# MotherBoard.net
KiCad netlist of a schematic drawn in Altium Designer
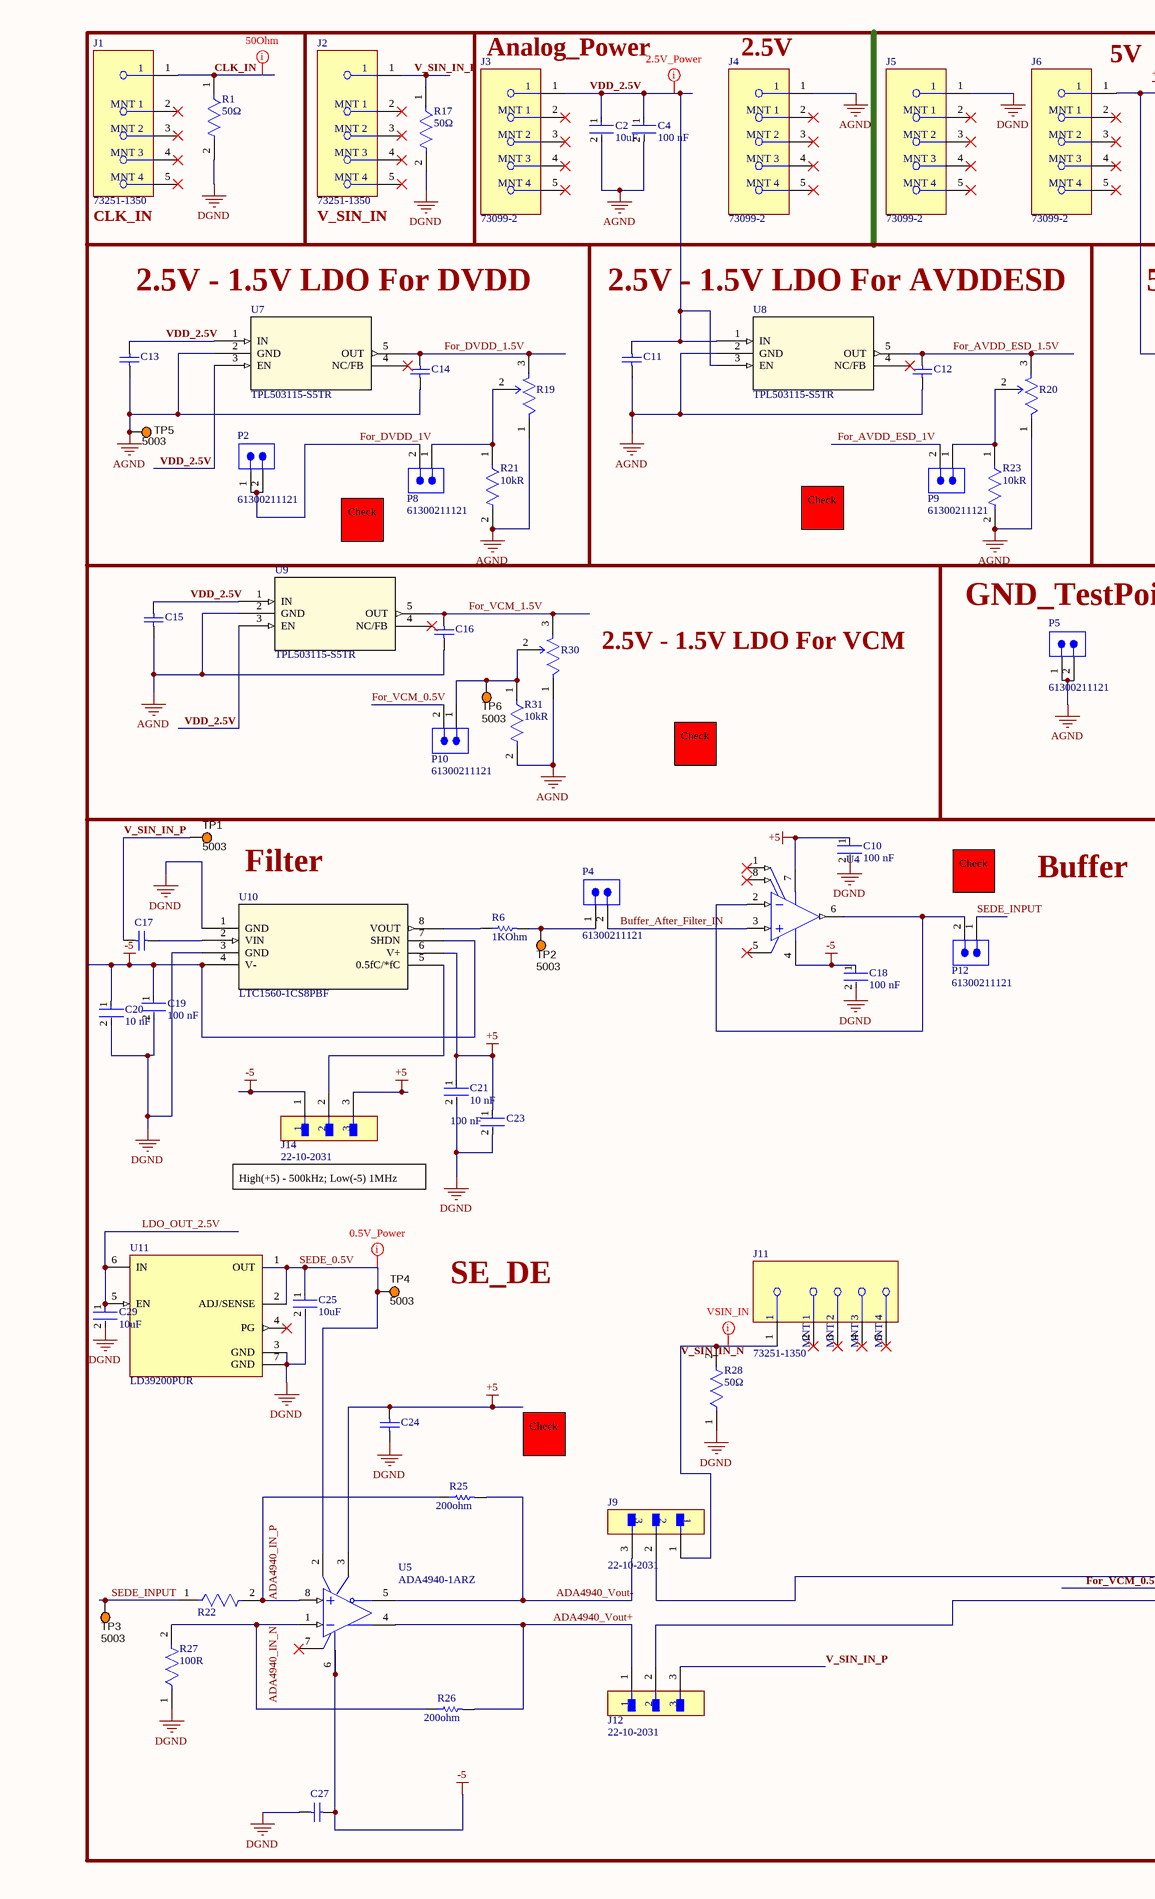
[diagram p0: MotherBoard.SchDoc, left]
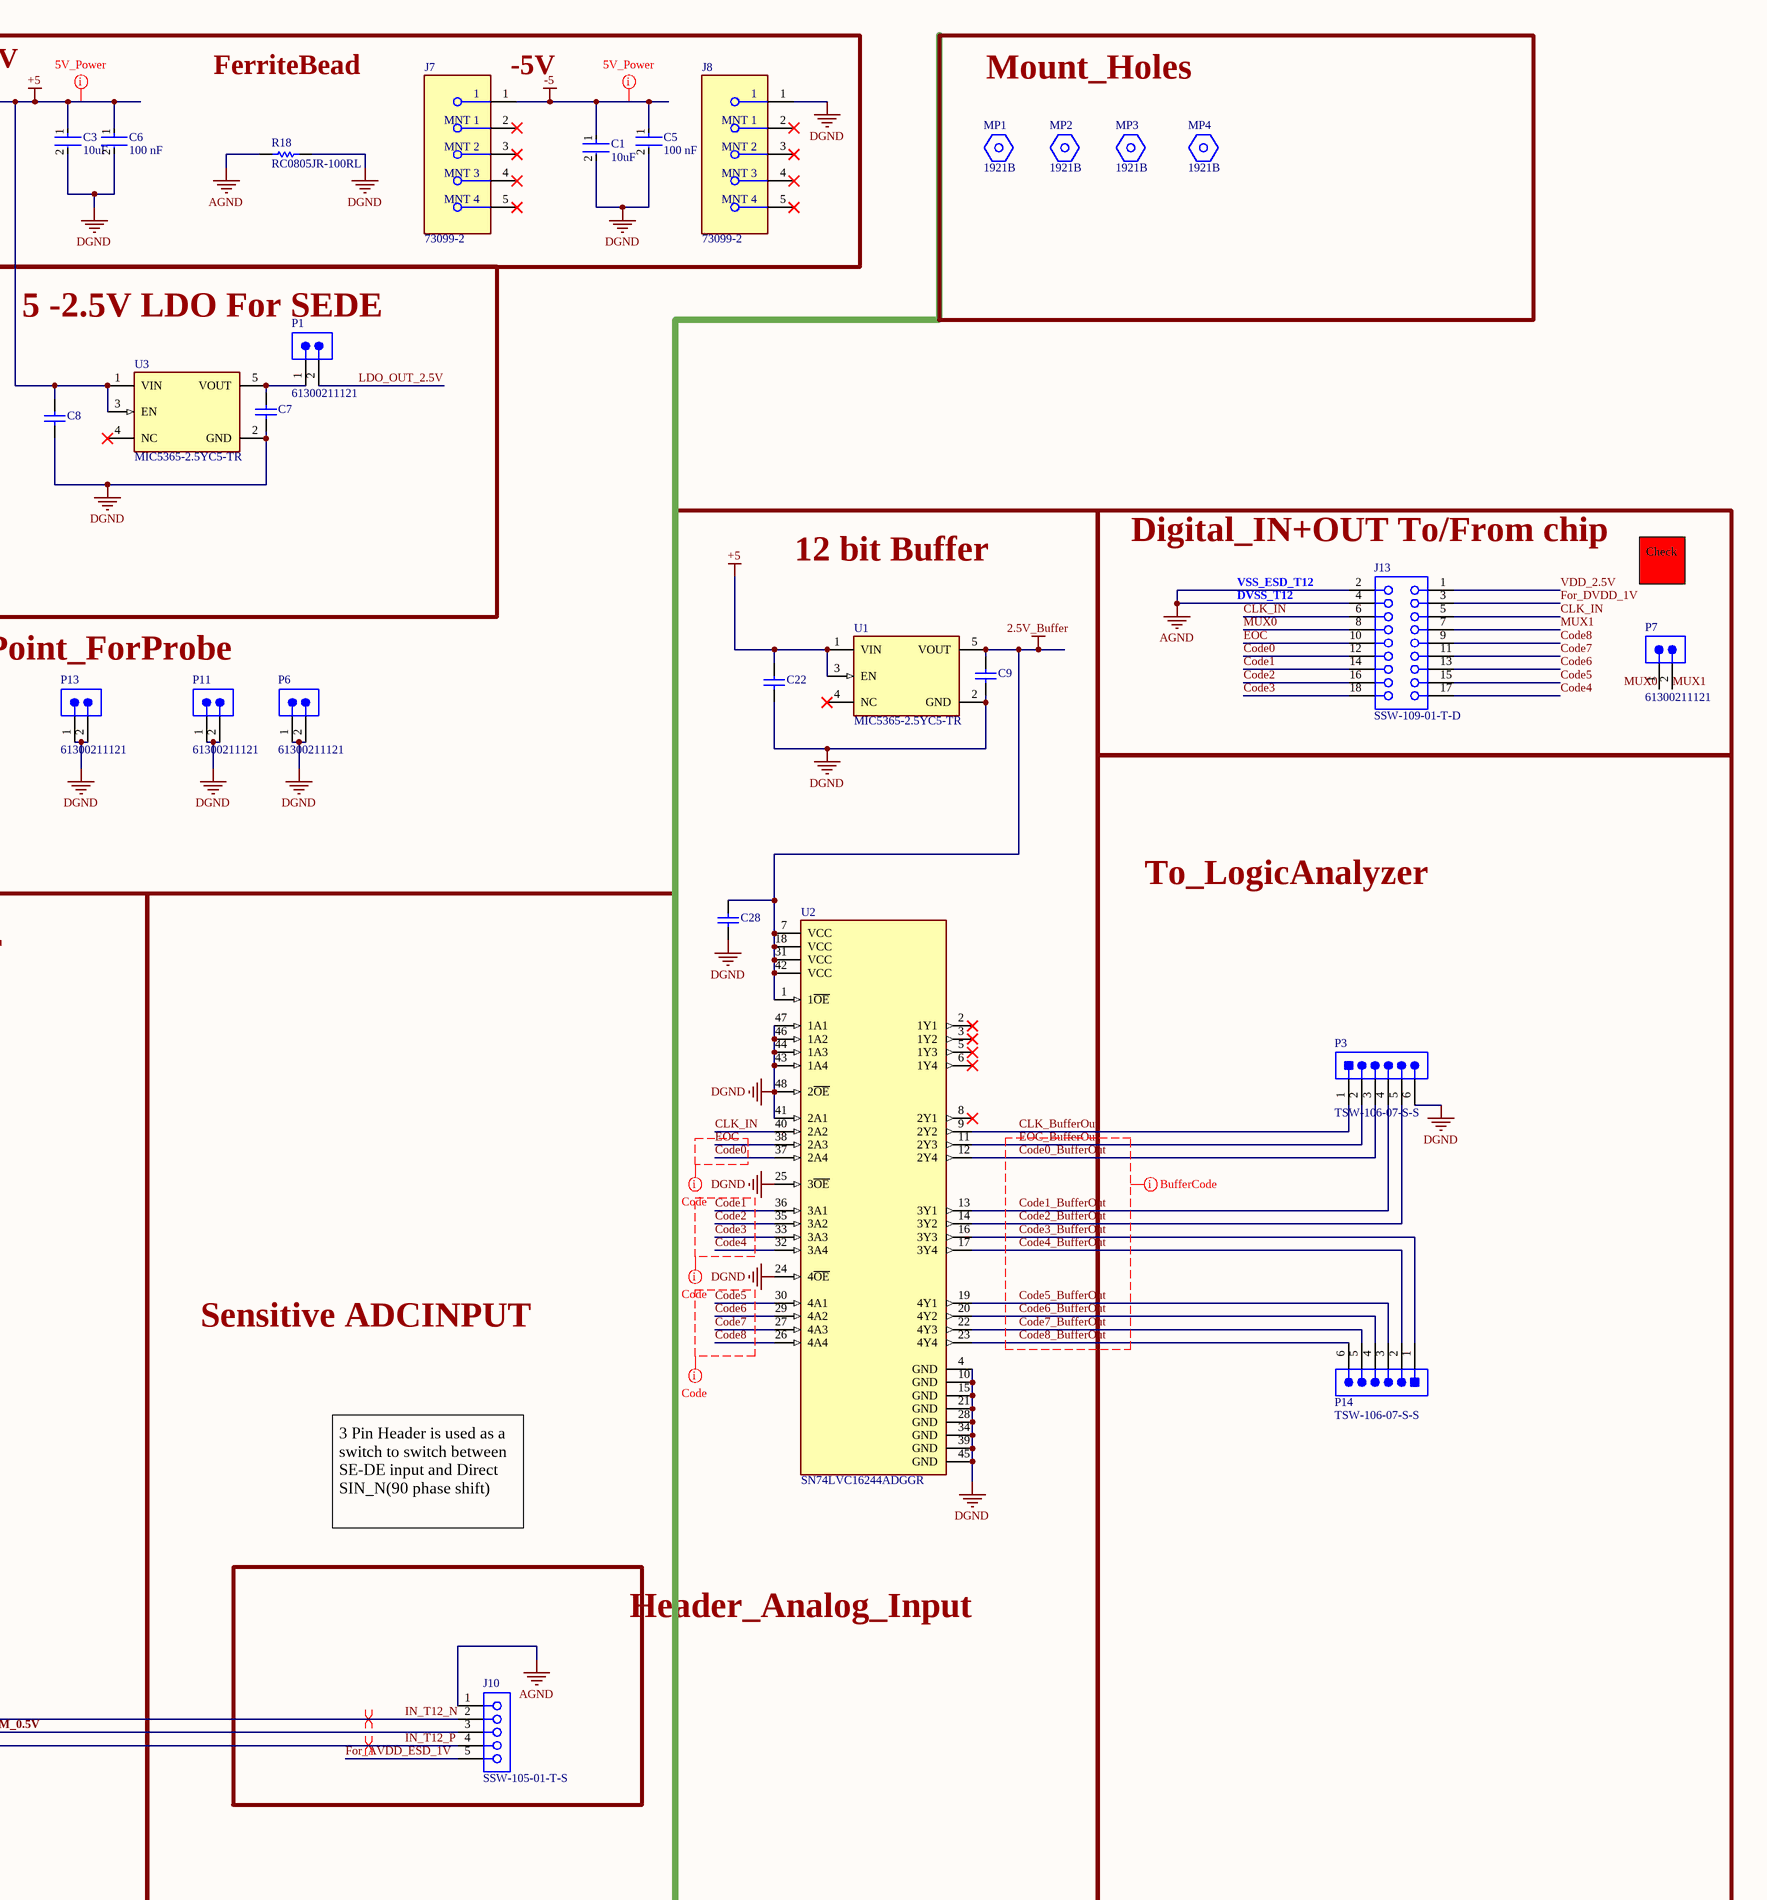
[diagram p1: MotherBoard.SchDoc, right]

(export (version "E")
  (design (tool "Eeschema 10.0.6"))
  (components
    (comp (ref "C1")
      (value "0805ZD106MAT2A")
      (footprint "FP-0805-L_2_01_0_2-W_1_25-MFG")
      (description "General Purpose Ceramic Capacitor, 0805, 10uF, 20%, X5R, 15%, 10V")
      (fields
        (field (name "CAPACITANCE") "10uF")
        (field (name "TOLERANCE") "20%")
        (field (name "VOLTAGE") "10V")
      )
      (libsource (lib "Altium Content Vault") (part "02cd4be3c70576c341d710602a673aa"))
    )
    (comp (ref "C2")
      (value "0805ZD106MAT2A")
      (footprint "FP-0805-L_2_01_0_2-W_1_25-MFG")
      (description "General Purpose Ceramic Capacitor, 0805, 10uF, 20%, X5R, 15%, 10V")
      (fields
        (field (name "CAPACITANCE") "10uF")
        (field (name "TOLERANCE") "20%")
        (field (name "VOLTAGE") "10V")
      )
      (libsource (lib "Altium Content Vault") (part "02cd4be3c70576c341d710602a673aa"))
    )
    (comp (ref "C3")
      (value "0805ZD106MAT2A")
      (footprint "FP-0805-L_2_01_0_2-W_1_25-MFG")
      (description "General Purpose Ceramic Capacitor, 0805, 10uF, 20%, X5R, 15%, 10V")
      (fields
        (field (name "CAPACITANCE") "10uF")
        (field (name "TOLERANCE") "20%")
        (field (name "VOLTAGE") "10V")
      )
      (libsource (lib "Altium Content Vault") (part "02cd4be3c70576c341d710602a673aa"))
    )
    (comp (ref "C4")
      (value "CC0805KRX7R8BB104")
      (footprint "FP-CC0805-0_85-MFG")
      (description "CAP CER 0.1UF 25V X7R 0805")
      (fields
        (field (name "TOLERANCE") "0.1")
        (field (name "MANUFACTURER") "Yageo")
        (field (name "CAPACITANCE") "100 nF")
      )
      (libsource (lib "Altium Content Vault") (part "11868f565c42a9108669ba33697ecf6"))
    )
    (comp (ref "C5")
      (value "CC0805KRX7R8BB104")
      (footprint "FP-CC0805-0_85-MFG")
      (description "CAP CER 0.1UF 25V X7R 0805")
      (fields
        (field (name "TOLERANCE") "0.1")
        (field (name "MANUFACTURER") "Yageo")
        (field (name "CAPACITANCE") "100 nF")
      )
      (libsource (lib "Altium Content Vault") (part "11868f565c42a9108669ba33697ecf6"))
    )
    (comp (ref "C6")
      (value "CC0805KRX7R8BB104")
      (footprint "FP-CC0805-0_85-MFG")
      (description "CAP CER 0.1UF 25V X7R 0805")
      (fields
        (field (name "TOLERANCE") "0.1")
        (field (name "MANUFACTURER") "Yageo")
        (field (name "CAPACITANCE") "100 nF")
      )
      (libsource (lib "Altium Content Vault") (part "11868f565c42a9108669ba33697ecf6"))
    )
    (comp (ref "C7")
      (value "0805ZC105KAZ2A")
      (footprint "CAPC2013X140X50LL20T25")
      (fields (field (name "MANUFACTURER") "AVX Interconnect / Elco"))
      (libsource (lib "Altium Content Vault") (part "CAP"))
    )
    (comp (ref "C8")
      (value "0805ZC105KAZ2A")
      (footprint "CAPC2013X140X50LL20T25")
      (fields (field (name "MANUFACTURER") "AVX Interconnect / Elco"))
      (libsource (lib "Altium Content Vault") (part "CAP"))
    )
    (comp (ref "C9")
      (value "0805ZC105KAZ2A")
      (footprint "CAPC2013X140X50LL20T25")
      (fields (field (name "MANUFACTURER") "AVX Interconnect / Elco"))
      (libsource (lib "Altium Content Vault") (part "CAP"))
    )
    (comp (ref "C10")
      (value "CC0805KRX7R8BB104")
      (footprint "FP-CC0805-0_85-MFG")
      (description "CAP CER 0.1UF 25V X7R 0805")
      (fields
        (field (name "TOLERANCE") "0.1")
        (field (name "MANUFACTURER") "Yageo")
        (field (name "CAPACITANCE") "100 nF")
      )
      (libsource (lib "Altium Content Vault") (part "11868f565c42a9108669ba33697ecf6"))
    )
    (comp (ref "C11")
      (value "0805ZC105KAZ2A")
      (footprint "CAPC2013X140X50LL20T25")
      (fields (field (name "MANUFACTURER") "AVX Interconnect / Elco"))
      (libsource (lib "Altium Content Vault") (part "CAP"))
    )
    (comp (ref "C12")
      (value "0805ZC105KAZ2A")
      (footprint "CAPC2013X140X50LL20T25")
      (fields (field (name "MANUFACTURER") "AVX Interconnect / Elco"))
      (libsource (lib "Altium Content Vault") (part "CAP"))
    )
    (comp (ref "C13")
      (value "0805ZC105KAZ2A")
      (footprint "CAPC2013X140X50LL20T25")
      (fields (field (name "MANUFACTURER") "AVX Interconnect / Elco"))
      (libsource (lib "Altium Content Vault") (part "CAP"))
    )
    (comp (ref "C14")
      (value "0805ZC105KAZ2A")
      (footprint "CAPC2013X140X50LL20T25")
      (fields (field (name "MANUFACTURER") "AVX Interconnect / Elco"))
      (libsource (lib "Altium Content Vault") (part "CAP"))
    )
    (comp (ref "C15")
      (value "0805ZC105KAZ2A")
      (footprint "CAPC2013X140X50LL20T25")
      (fields (field (name "MANUFACTURER") "AVX Interconnect / Elco"))
      (libsource (lib "Altium Content Vault") (part "CAP"))
    )
    (comp (ref "C16")
      (value "0805ZC105KAZ2A")
      (footprint "CAPC2013X140X50LL20T25")
      (fields (field (name "MANUFACTURER") "AVX Interconnect / Elco"))
      (libsource (lib "Altium Content Vault") (part "CAP"))
    )
    (comp (ref "C17")
      (value "VJ0805D561KXBAJ")
      (footprint "CAPC2013X145X48ML20T23")
      (fields (field (name "MANUFACTURER") "Vitramon"))
      (libsource (lib "Altium Content Vault") (part "CAP"))
    )
    (comp (ref "C18")
      (value "CC0805KRX7R8BB104")
      (footprint "FP-CC0805-0_85-MFG")
      (description "CAP CER 0.1UF 25V X7R 0805")
      (fields
        (field (name "TOLERANCE") "0.1")
        (field (name "MANUFACTURER") "Yageo")
        (field (name "CAPACITANCE") "100 nF")
      )
      (libsource (lib "Altium Content Vault") (part "11868f565c42a9108669ba33697ecf6"))
    )
    (comp (ref "C19")
      (value "CC0805KRX7R8BB104")
      (footprint "FP-CC0805-0_85-MFG")
      (description "CAP CER 0.1UF 25V X7R 0805")
      (fields
        (field (name "TOLERANCE") "0.1")
        (field (name "MANUFACTURER") "Yageo")
        (field (name "CAPACITANCE") "100 nF")
      )
      (libsource (lib "Altium Content Vault") (part "11868f565c42a9108669ba33697ecf6"))
    )
    (comp (ref "C20")
      (value "CC0805KRX7R9BB103")
      (footprint "FP-CC0805-0_85-MFG")
      (description "CAP CER 10000PF 50V X7R 0805")
      (fields
        (field (name "CAPACITANCE") "10 nF")
        (field (name "OCTOPART") "https://octopart.com/cc0805krx7r9bb103-yageo-192989")
        (field (name "MANUFACTURER") "Yageo")
      )
      (libsource (lib "Altium Content Vault") (part "11868f565c42a9108669ba33697ecf6"))
    )
    (comp (ref "C21")
      (value "CC0805KRX7R9BB103")
      (footprint "FP-CC0805-0_85-MFG")
      (description "CAP CER 10000PF 50V X7R 0805")
      (fields
        (field (name "CAPACITANCE") "10 nF")
        (field (name "OCTOPART") "https://octopart.com/cc0805krx7r9bb103-yageo-192989")
        (field (name "MANUFACTURER") "Yageo")
      )
      (libsource (lib "Altium Content Vault") (part "11868f565c42a9108669ba33697ecf6"))
    )
    (comp (ref "C22")
      (value "0805ZC105KAZ2A")
      (footprint "CAPC2013X140X50LL20T25")
      (fields (field (name "MANUFACTURER") "AVX Interconnect / Elco"))
      (libsource (lib "Altium Content Vault") (part "CAP"))
    )
    (comp (ref "C23")
      (value "CC0805KRX7R8BB104")
      (footprint "FP-CC0805-0_85-MFG")
      (description "CAP CER 0.1UF 25V X7R 0805")
      (fields
        (field (name "TOLERANCE") "0.1")
        (field (name "MANUFACTURER") "Yageo")
        (field (name "CAPACITANCE") "100 nF")
      )
      (libsource (lib "Altium Content Vault") (part "11868f565c42a9108669ba33697ecf6"))
    )
    (comp (ref "C24")
      (value "0805ZC105KAZ2A")
      (footprint "CAPC2013X140X50LL20T25")
      (fields (field (name "MANUFACTURER") "AVX Interconnect / Elco"))
      (libsource (lib "Altium Content Vault") (part "CAP"))
    )
    (comp (ref "C25")
      (value "0805ZD106MAT2A")
      (footprint "FP-0805-L_2_01_0_2-W_1_25-MFG")
      (description "General Purpose Ceramic Capacitor, 0805, 10uF, 20%, X5R, 15%, 10V")
      (fields
        (field (name "CAPACITANCE") "10uF")
        (field (name "TOLERANCE") "20%")
        (field (name "VOLTAGE") "10V")
      )
      (libsource (lib "Altium Content Vault") (part "02cd4be3c70576c341d710602a673aa"))
    )
    (comp (ref "C27")
      (value "0805ZC105KAZ2A")
      (footprint "CAPC2013X140X50LL20T25")
      (fields (field (name "MANUFACTURER") "AVX Interconnect / Elco"))
      (libsource (lib "Altium Content Vault") (part "CAP"))
    )
    (comp (ref "C28")
      (value "0805ZC105KAZ2A")
      (footprint "CAPC2013X140X50LL20T25")
      (fields (field (name "MANUFACTURER") "AVX Interconnect / Elco"))
      (libsource (lib "Altium Content Vault") (part "CAP"))
    )
    (comp (ref "C29")
      (value "0805ZD106MAT2A")
      (footprint "FP-0805-L_2_01_0_2-W_1_25-MFG")
      (description "General Purpose Ceramic Capacitor, 0805, 10uF, 20%, X5R, 15%, 10V")
      (fields
        (field (name "CAPACITANCE") "10uF")
        (field (name "TOLERANCE") "20%")
        (field (name "VOLTAGE") "10V")
      )
      (libsource (lib "Altium Content Vault") (part "02cd4be3c70576c341d710602a673aa"))
    )
    (comp (ref "J1")
      (value "73251-1350")
      (footprint "FP-73251-1350-MFG")
      (description "CONN SMA JACK STR 50 OHM SMD")
      (fields
        (field (name "OCTOPART") "https://octopart.com/73251-1350-molex-5414390")
        (field (name "MANUFACTURER") "Molex")
      )
      (libsource (lib "Altium Content Vault") (part "474d33b8a96b1ade9ed6dd87a2b06d4"))
    )
    (comp (ref "J2")
      (value "73251-1350")
      (footprint "FP-73251-1350-MFG")
      (description "CONN SMA JACK STR 50 OHM SMD")
      (fields
        (field (name "OCTOPART") "https://octopart.com/73251-1350-molex-5414390")
        (field (name "MANUFACTURER") "Molex")
      )
      (libsource (lib "Altium Content Vault") (part "474d33b8a96b1ade9ed6dd87a2b06d4"))
    )
    (comp (ref "J3")
      (value "73099-2")
      (footprint "FP-73099-2-MFG")
      (description "R/A 4MM MOUNTG SAFE JACK/PCB RED")
      (libsource (lib "Altium Content Vault") (part "9c40ac4d87bbbe9fcb330bd20f98ca3"))
    )
    (comp (ref "J4")
      (value "73099-2")
      (footprint "FP-73099-2-MFG")
      (description "R/A 4MM MOUNTG SAFE JACK/PCB RED")
      (libsource (lib "Altium Content Vault") (part "9c40ac4d87bbbe9fcb330bd20f98ca3"))
    )
    (comp (ref "J5")
      (value "73099-2")
      (footprint "FP-73099-2-MFG")
      (description "R/A 4MM MOUNTG SAFE JACK/PCB RED")
      (libsource (lib "Altium Content Vault") (part "9c40ac4d87bbbe9fcb330bd20f98ca3"))
    )
    (comp (ref "J6")
      (value "73099-2")
      (footprint "FP-73099-2-MFG")
      (description "R/A 4MM MOUNTG SAFE JACK/PCB RED")
      (libsource (lib "Altium Content Vault") (part "9c40ac4d87bbbe9fcb330bd20f98ca3"))
    )
    (comp (ref "J7")
      (value "73099-2")
      (footprint "FP-73099-2-MFG")
      (description "R/A 4MM MOUNTG SAFE JACK/PCB RED")
      (libsource (lib "Altium Content Vault") (part "9c40ac4d87bbbe9fcb330bd20f98ca3"))
    )
    (comp (ref "J8")
      (value "73099-2")
      (footprint "FP-73099-2-MFG")
      (description "R/A 4MM MOUNTG SAFE JACK/PCB RED")
      (libsource (lib "Altium Content Vault") (part "9c40ac4d87bbbe9fcb330bd20f98ca3"))
    )
    (comp (ref "J9")
      (value "22-10-2031")
      (footprint "FP-22-10-2031-MFG")
      (description "CONN HEADER VERT 3POS 2.54MM")
      (libsource (lib "") (part "0d3f023dd272f625e17a2be33dea85f_1"))
    )
    (comp (ref "J10")
      (value "SSW-105-01-T-S")
      (footprint "SMTC-SSW-105-01-X-S")
      (description "SQ Post Socket, Through-hole, Vertical, -55 to 105 degC, 2.54mm Pitch, 5-Pin, Female, RoHS")
      (fields (field (name "MANUFACTURER") "Samtec"))
      (libsource (lib "Altium Content Vault") (part "SMTC-SSW-105-X-X-S"))
    )
    (comp (ref "J11")
      (value "73251-1350")
      (footprint "FP-73251-1350-MFG")
      (description "CONN SMA JACK STR 50 OHM SMD")
      (fields
        (field (name "OCTOPART") "https://octopart.com/73251-1350-molex-5414390")
        (field (name "MANUFACTURER") "Molex")
      )
      (libsource (lib "") (part "474d33b8a96b1ade9ed6dd87a2b06d4_1"))
    )
    (comp (ref "J12")
      (value "22-10-2031")
      (footprint "FP-22-10-2031-MFG")
      (description "CONN HEADER VERT 3POS 2.54MM")
      (libsource (lib "Altium Content Vault") (part "0d3f023dd272f625e17a2be33dea85f"))
    )
    (comp (ref "J13")
      (value "SSW-109-01-T-D")
      (footprint "SMTC-SSW-109-01-X-D")
      (description "SQ Post Socket, Through-hole, Vertical, -55 to 105 degC, 2.54mm Pitch, 18-Pin, Female, RoHS")
      (fields (field (name "MANUFACTURER") "Samtec"))
      (libsource (lib "Altium Content Vault") (part "SMTC-SSW-109-01-X-D"))
    )
    (comp (ref "J14")
      (value "22-10-2031")
      (footprint "FP-22-10-2031-MFG")
      (description "CONN HEADER VERT 3POS 2.54MM")
      (libsource (lib "Altium Content Vault") (part "0d3f023dd272f625e17a2be33dea85f"))
    )
    (comp (ref "MP1")
      (value "1921B")
      (footprint "FP-1921B-MFG")
      (description "1921B Standoff, 1/4 Hex, Female, Threaded 4-40, Length .500, Stainless Steel")
      (libsource (lib "Altium Content Vault") (part "08a03163f22740170b61ca9211e1d1e"))
    )
    (comp (ref "MP2")
      (value "1921B")
      (footprint "FP-1921B-MFG")
      (description "1921B Standoff, 1/4 Hex, Female, Threaded 4-40, Length .500, Stainless Steel")
      (libsource (lib "Altium Content Vault") (part "08a03163f22740170b61ca9211e1d1e"))
    )
    (comp (ref "MP3")
      (value "1921B")
      (footprint "FP-1921B-MFG")
      (description "1921B Standoff, 1/4 Hex, Female, Threaded 4-40, Length .500, Stainless Steel")
      (libsource (lib "Altium Content Vault") (part "08a03163f22740170b61ca9211e1d1e"))
    )
    (comp (ref "MP4")
      (value "1921B")
      (footprint "FP-1921B-MFG")
      (description "1921B Standoff, 1/4 Hex, Female, Threaded 4-40, Length .500, Stainless Steel")
      (libsource (lib "Altium Content Vault") (part "08a03163f22740170b61ca9211e1d1e"))
    )
    (comp (ref "P1")
      (value "61300211121")
      (footprint "61300211121")
      (libsource (lib "Altium Content Vault") (part "Header_Male_1R_02P"))
    )
    (comp (ref "P2")
      (value "61300211121")
      (footprint "61300211121")
      (libsource (lib "Altium Content Vault") (part "Header_Male_1R_02P"))
    )
    (comp (ref "P3")
      (value "TSW-106-07-S-S")
      (footprint "SMTC-TSW-106-07-S-S_V")
      (fields (field (name "MANUFACTURER") "Samtec"))
      (libsource (lib "Altium Content Vault") (part "CN-1P-M-R6"))
    )
    (comp (ref "P4")
      (value "61300211121")
      (footprint "61300211121")
      (libsource (lib "Altium Content Vault") (part "Header_Male_1R_02P"))
    )
    (comp (ref "P5")
      (value "61300211121")
      (footprint "61300211121")
      (libsource (lib "Altium Content Vault") (part "Header_Male_1R_02P"))
    )
    (comp (ref "P6")
      (value "61300211121")
      (footprint "61300211121")
      (libsource (lib "Altium Content Vault") (part "Header_Male_1R_02P"))
    )
    (comp (ref "P7")
      (value "61300211121")
      (footprint "61300211121")
      (libsource (lib "Altium Content Vault") (part "Header_Male_1R_02P"))
    )
    (comp (ref "P8")
      (value "61300211121")
      (footprint "61300211121")
      (libsource (lib "Altium Content Vault") (part "Header_Male_1R_02P"))
    )
    (comp (ref "P9")
      (value "61300211121")
      (footprint "61300211121")
      (libsource (lib "Altium Content Vault") (part "Header_Male_1R_02P"))
    )
    (comp (ref "P10")
      (value "61300211121")
      (footprint "61300211121")
      (libsource (lib "Altium Content Vault") (part "Header_Male_1R_02P"))
    )
    (comp (ref "P11")
      (value "61300211121")
      (footprint "61300211121")
      (libsource (lib "Altium Content Vault") (part "Header_Male_1R_02P"))
    )
    (comp (ref "P12")
      (value "61300211121")
      (footprint "61300211121")
      (libsource (lib "Altium Content Vault") (part "Header_Male_1R_02P"))
    )
    (comp (ref "P13")
      (value "61300211121")
      (footprint "61300211121")
      (libsource (lib "Altium Content Vault") (part "Header_Male_1R_02P"))
    )
    (comp (ref "P14")
      (value "TSW-106-07-S-S")
      (footprint "SMTC-TSW-106-07-S-S_V")
      (fields (field (name "MANUFACTURER") "Samtec"))
      (libsource (lib "") (part "CN-1P-M-R6_1"))
    )
    (comp (ref "R1")
      (value "CRCW080550R0FKTA")
      (footprint "FP-D12-CRCW0805-MFG")
      (description "CRCW080550R0FKTA Res Thick Film 0805 50 Ohm 1% 0.125W(1/8W) ±100ppm/C Pad SMD Automotive T/R")
      (fields (field (name "TOLERANCE") "1%") (field (name "RESISTANCE") "50Ω"))
      (libsource (lib "Altium Content Vault") (part "1029c3af85768c4190bb7ad29bc67b5"))
    )
    (comp (ref "R6")
      (value "RC0805FR-071KL")
      (footprint "RESC2013X60X35ML10T20")
      (description "Chip Resistor, 1 KOhm, +/- 1%, 125 mW, -55 to 155 degC, 0805 (2012 Metric), RoHS, Tape and Reel")
      (fields
        (field (name "RESISTANCE") "1KOhm")
        (field (name "TOLERANCE") "1%")
        (field (name "MANUFACTURER") "Yageo")
      )
      (libsource (lib "Altium Content Vault") (part "RES-2"))
    )
    (comp (ref "R17")
      (value "CRCW080550R0FKTA")
      (footprint "FP-D12-CRCW0805-MFG")
      (description "CRCW080550R0FKTA Res Thick Film 0805 50 Ohm 1% 0.125W(1/8W) ±100ppm/C Pad SMD Automotive T/R")
      (fields (field (name "TOLERANCE") "1%") (field (name "RESISTANCE") "50Ω"))
      (libsource (lib "Altium Content Vault") (part "1029c3af85768c4190bb7ad29bc67b5"))
    )
    (comp (ref "R18")
      (value "RC0805JR-100RL")
      (footprint "RESC2013X60X35LL10T20")
      (description "Chip Resistor, 0 Ohm, +/- 5%, 125 mW, -55 to 155 degC, 0805 (2012 Metric), RoHS, Tape and Reel")
      (fields (field (name "MANUFACTURER") "Yageo"))
      (libsource (lib "Altium Content Vault") (part "RES-2"))
    )
    (comp (ref "R19")
      (value "3296W-1-253LF")
      (footprint "FP-3296W-MFG")
      (description "TRIMMER 25K OHM 0.5W PC PIN TOP")
      (fields (field (name "TOLERANCE") "10%"))
      (libsource (lib "Altium Content Vault") (part "2dcfd2547301a7d3209a5e99acfd772"))
    )
    (comp (ref "R20")
      (value "3296W-1-253LF")
      (footprint "FP-3296W-MFG")
      (description "TRIMMER 25K OHM 0.5W PC PIN TOP")
      (fields (field (name "TOLERANCE") "10%"))
      (libsource (lib "Altium Content Vault") (part "2dcfd2547301a7d3209a5e99acfd772"))
    )
    (comp (ref "R21")
      (value "CRCW080510K0FKEA")
      (footprint "FP-CRCW0805-e3-IPC_A")
      (description "RES Thick Film, 10kΩ, 1%, 0.125W, 100ppm/°C, 0805")
      (fields (field (name "RESISTANCE") "10kR") (field (name "TOLERANCE") "1%"))
      (libsource (lib "Altium Content Vault") (part "1029c3af85768c4190bb7ad29bc67b5"))
    )
    (comp (ref "R22")
      (value "CRCW0805100RFKEAHP")
      (footprint "FP-CRCW0805-HPe3-IPC_A")
      (description "RES Thick Film, 100Ω, 1%, 0.5W, 100ppm/°C, 0805")
      (fields (field (name "TOLERANCE") "1%"))
      (libsource (lib "Altium Content Vault") (part "1029c3af85768c4190bb7ad29bc67b5"))
    )
    (comp (ref "R23")
      (value "CRCW080510K0FKEA")
      (footprint "FP-CRCW0805-e3-IPC_A")
      (description "RES Thick Film, 10kΩ, 1%, 0.125W, 100ppm/°C, 0805")
      (fields (field (name "RESISTANCE") "10kR") (field (name "TOLERANCE") "1%"))
      (libsource (lib "Altium Content Vault") (part "1029c3af85768c4190bb7ad29bc67b5"))
    )
    (comp (ref "R25")
      (value "200ohm")
      (footprint "RESC2013X70X40ML20T20")
      (fields (field (name "MANUFACTURER") "Panasonic") (field (name "PART NUMBER") "ERJ-6ENF2000V"))
      (libsource (lib "Altium Content Vault") (part "RES"))
    )
    (comp (ref "R26")
      (value "200ohm")
      (footprint "RESC2013X70X40ML20T20")
      (fields (field (name "MANUFACTURER") "Panasonic") (field (name "PART NUMBER") "ERJ-6ENF2000V"))
      (libsource (lib "Altium Content Vault") (part "RES"))
    )
    (comp (ref "R27")
      (value "CRCW0805100RFKEAHP")
      (footprint "FP-CRCW0805-HPe3-IPC_A")
      (description "RES Thick Film, 100Ω, 1%, 0.5W, 100ppm/°C, 0805")
      (fields (field (name "TOLERANCE") "1%") (field (name "RESISTANCE") "100R"))
      (libsource (lib "Altium Content Vault") (part "1029c3af85768c4190bb7ad29bc67b5"))
    )
    (comp (ref "R28")
      (value "CRCW080550R0FKTA")
      (footprint "FP-D12-CRCW0805-MFG")
      (description "CRCW080550R0FKTA Res Thick Film 0805 50 Ohm 1% 0.125W(1/8W) ±100ppm/C Pad SMD Automotive T/R")
      (fields (field (name "TOLERANCE") "1%") (field (name "RESISTANCE") "50Ω"))
      (libsource (lib "Altium Content Vault") (part "1029c3af85768c4190bb7ad29bc67b5"))
    )
    (comp (ref "R30")
      (value "3296W-1-253LF")
      (footprint "FP-3296W-MFG")
      (description "TRIMMER 25K OHM 0.5W PC PIN TOP")
      (fields (field (name "TOLERANCE") "10%"))
      (libsource (lib "Altium Content Vault") (part "2dcfd2547301a7d3209a5e99acfd772"))
    )
    (comp (ref "R31")
      (value "CRCW080510K0FKEA")
      (footprint "FP-CRCW0805-e3-IPC_A")
      (description "RES Thick Film, 10kΩ, 1%, 0.125W, 100ppm/°C, 0805")
      (fields (field (name "RESISTANCE") "10kR") (field (name "TOLERANCE") "1%"))
      (libsource (lib "Altium Content Vault") (part "1029c3af85768c4190bb7ad29bc67b5"))
    )
    (comp (ref "TP1")
      (value "5003")
      (footprint "KSTN-5003")
      (description "Test Point, Orange, 1-Pin THD, RoHS")
      (libsource (lib "Altium Content Vault") (part "TESTPOINT_ORANGE"))
    )
    (comp (ref "TP2")
      (value "5003")
      (footprint "KSTN-5003")
      (description "Test Point, Orange, 1-Pin THD, RoHS")
      (libsource (lib "Altium Content Vault") (part "TESTPOINT_ORANGE"))
    )
    (comp (ref "TP3")
      (value "5003")
      (footprint "KSTN-5003")
      (description "Test Point, Orange, 1-Pin THD, RoHS")
      (libsource (lib "Altium Content Vault") (part "TESTPOINT_ORANGE"))
    )
    (comp (ref "TP4")
      (value "5003")
      (footprint "KSTN-5003")
      (description "Test Point, Orange, 1-Pin THD, RoHS")
      (libsource (lib "Altium Content Vault") (part "TESTPOINT_ORANGE"))
    )
    (comp (ref "TP5")
      (value "5003")
      (footprint "KSTN-5003")
      (description "Test Point, Orange, 1-Pin THD, RoHS")
      (libsource (lib "Altium Content Vault") (part "TESTPOINT_ORANGE"))
    )
    (comp (ref "TP6")
      (value "5003")
      (footprint "KSTN-5003")
      (description "Test Point, Orange, 1-Pin THD, RoHS")
      (libsource (lib "Altium Content Vault") (part "TESTPOINT_ORANGE"))
    )
    (comp (ref "U1")
      (value "MIC5365-2.5YC5-TR")
      (footprint "FP-SC70-5LD-PL-1-MFG")
      (description "IC REG LINEAR 2.5V 150MA SC70-5")
      (libsource (lib "Altium Content Vault") (part "62bd28826b54e3bd5f89c9ba9bda61c"))
    )
    (comp (ref "U2")
      (value "SN74LVC16244ADGGR")
      (footprint "FP-DGG0048A-IPC_B")
      (description "IC BUF NON-INVERT 3.6V 48TSSOP")
      (libsource (lib "Altium Content Vault") (part "34c0b7439352cfd7100edb36af6fd87"))
    )
    (comp (ref "U3")
      (value "MIC5365-2.5YC5-TR")
      (footprint "FP-SC70-5LD-PL-1-MFG")
      (description "IC REG LINEAR 2.5V 150MA SC70-5")
      (libsource (lib "Altium Content Vault") (part "62bd28826b54e3bd5f89c9ba9bda61c"))
    )
    (comp (ref "U4")
      (value "LT1360CS8#PBF")
      (footprint "LT-S8-8_L")
      (fields
        (field (name "LINEAR TECHNOLOGY PART NUMBER") "LT1360")
        (field (name "MANUFACTURER") "Linear Technology")
      )
      (libsource (lib "Altium Content Vault") (part "LT-LT135X-LT136X-8"))
    )
    (comp (ref "U5")
      (value "ADA4940-1ARZ")
      (footprint "ADI-R-8_L")
      (libsource (lib "Altium Content Vault") (part "ADI-ADA4940-R-8"))
    )
    (comp (ref "U7")
      (value "TPL503115-S5TR")
      (footprint "SOT23-5-A_TPK")
      (description "No Description Available")
      (libsource (lib "TPL503115-S5TR") (part "TPL503115-S5TR"))
    )
    (comp (ref "U8")
      (value "TPL503115-S5TR")
      (footprint "SOT23-5-A_TPK")
      (description "No Description Available")
      (libsource (lib "TPL503115-S5TR") (part "TPL503115-S5TR"))
    )
    (comp (ref "U9")
      (value "TPL503115-S5TR")
      (footprint "SOT23-5-A_TPK")
      (description "No Description Available")
      (libsource (lib "TPL503115-S5TR") (part "TPL503115-S5TR"))
    )
    (comp (ref "U10")
      (value "LTC1560-1CS8PBF")
      (footprint "SO-8_S_LIT-M")
      (description "No Description Available")
      (libsource (lib "LTC1560-1CS8PBF") (part "LTC1560-1CS8PBF"))
    )
    (comp (ref "U11")
      (value "LD39200PUR")
      (footprint "FP-DFN6-7946637-IPC_A")
      (description "IC REG LINEAR POS ADJ 2A 6DFN")
      (fields
        (field (name "MANUFACTURER") "STMicroelectronics")
        (field (name "OCTOPART") "https://octopart.com/ld39200pur-stmicroelectronics-77085816")
      )
      (libsource (lib "Altium Content Vault") (part "edb6347640e7083f10f76e8a04eaca8"))
    )
  )
  (nets
    (net (code "1") (name "+5") (class "Default")
      (node (ref "C10") (pin "1") (pinfunction "1_1") (pintype "passive"))
      (node (ref "C21") (pin "1") (pinfunction "1_1") (pintype "passive"))
      (node (ref "C22") (pin "2") (pinfunction "2_2") (pintype "passive"))
      (node (ref "C23") (pin "1") (pinfunction "1_1") (pintype "passive"))
      (node (ref "C24") (pin "2") (pinfunction "2_2") (pintype "passive"))
      (node (ref "C3") (pin "1") (pinfunction "1_1") (pintype "passive"))
      (node (ref "C6") (pin "1") (pinfunction "1_1") (pintype "passive"))
      (node (ref "C8") (pin "2") (pinfunction "2_2") (pintype "passive"))
      (node (ref "J14") (pin "3") (pinfunction "3_3") (pintype "passive"))
      (node (ref "J6") (pin "1") (pinfunction "1_1") (pintype "passive"))
      (node (ref "U1") (pin "1") (pinfunction "VIN_1") (pintype "power_in"))
      (node (ref "U1") (pin "3") (pinfunction "EN_3") (pintype "input"))
      (node (ref "U10") (pin "6") (pinfunction "V+_6") (pintype "power_in"))
      (node (ref "U3") (pin "1") (pinfunction "VIN_1") (pintype "power_in"))
      (node (ref "U3") (pin "3") (pinfunction "EN_3") (pintype "input"))
      (node (ref "U4") (pin "7") (pinfunction "V+_7") (pintype "power_in"))
      (node (ref "U5") (pin "3") (pinfunction "VS+_3") (pintype "power_in"))
    )
    (net (code "2") (name "-5") (class "Default")
      (node (ref "C1") (pin "1") (pinfunction "1_1") (pintype "passive"))
      (node (ref "C18") (pin "1") (pinfunction "1_1") (pintype "passive"))
      (node (ref "C19") (pin "1") (pinfunction "1_1") (pintype "passive"))
      (node (ref "C20") (pin "1") (pinfunction "1_1") (pintype "passive"))
      (node (ref "C27") (pin "2") (pinfunction "2_2") (pintype "passive"))
      (node (ref "C5") (pin "1") (pinfunction "1_1") (pintype "passive"))
      (node (ref "J14") (pin "1") (pinfunction "1_1") (pintype "passive"))
      (node (ref "J7") (pin "1") (pinfunction "1_1") (pintype "passive"))
      (node (ref "U10") (pin "4") (pinfunction "V-_4") (pintype "power_in"))
      (node (ref "U10") (pin "7") (pinfunction "SHDN_7") (pintype "passive"))
      (node (ref "U4") (pin "4") (pinfunction "V-_4") (pintype "power_in"))
      (node (ref "U5") (pin "6") (pinfunction "VS-_6") (pintype "power_in"))
    )
    (net (code "3") (name "/ADA4940_IN_N") (class "Default")
      (node (ref "R26") (pin "1") (pinfunction "1_1") (pintype "passive"))
      (node (ref "R27") (pin "2") (pinfunction "2_2") (pintype "passive"))
      (node (ref "U5") (pin "1") (pinfunction "IN-_1") (pintype "input"))
    )
    (net (code "4") (name "/ADA4940_IN_P") (class "Default")
      (node (ref "R22") (pin "2") (pinfunction "2_2") (pintype "passive"))
      (node (ref "R25") (pin "1") (pinfunction "1_1") (pintype "passive"))
      (node (ref "U5") (pin "8") (pinfunction "IN+_8") (pintype "input"))
    )
    (net (code "5") (name "/ADA4940_Vout+") (class "Default")
      (node (ref "J12") (pin "1") (pinfunction "1_1") (pintype "passive"))
      (node (ref "R26") (pin "2") (pinfunction "2_2") (pintype "passive"))
      (node (ref "U5") (pin "4") (pinfunction "OUT+_4") (pintype "tri_state"))
    )
    (net (code "6") (name "/ADA4940_Vout-") (class "Default")
      (node (ref "J9") (pin "3") (pinfunction "3_3") (pintype "passive"))
      (node (ref "R25") (pin "2") (pinfunction "2_2") (pintype "passive"))
      (node (ref "U5") (pin "5") (pinfunction "OUT-_5") (pintype "tri_state"))
    )
    (net (code "7") (name "/Buffer_After_Filter_IN") (class "Default")
      (node (ref "P4") (pin "2") (pinfunction "2_2") (pintype "passive"))
      (node (ref "U4") (pin "3") (pinfunction "+IN_3") (pintype "input"))
    )
    (net (code "8") (name "/CLK_BufferOut") (class "Default")
      (node (ref "P3") (pin "1") (pinfunction "1_1") (pintype "passive"))
      (node (ref "U2") (pin "9") (pinfunction "2Y2_9") (pintype "output"))
    )
    (net (code "9") (name "/CLK_IN") (class "Default")
      (node (ref "J1") (pin "1") (pinfunction "1_1") (pintype "passive"))
      (node (ref "J13") (pin "5") (pinfunction "5_5") (pintype "passive"))
      (node (ref "J13") (pin "6") (pinfunction "6_6") (pintype "passive"))
      (node (ref "R1") (pin "1") (pinfunction "1_1") (pintype "passive"))
      (node (ref "U2") (pin "40") (pinfunction "2A2_40") (pintype "input"))
    )
    (net (code "10") (name "/Code0") (class "Default")
      (node (ref "J13") (pin "12") (pinfunction "12_12") (pintype "passive"))
      (node (ref "U2") (pin "37") (pinfunction "2A4_37") (pintype "input"))
    )
    (net (code "11") (name "/Code0_BufferOut") (class "Default")
      (node (ref "P3") (pin "3") (pinfunction "3_3") (pintype "passive"))
      (node (ref "U2") (pin "12") (pinfunction "2Y4_12") (pintype "output"))
    )
    (net (code "12") (name "/Code1") (class "Default")
      (node (ref "J13") (pin "14") (pinfunction "14_14") (pintype "passive"))
      (node (ref "U2") (pin "36") (pinfunction "3A1_36") (pintype "input"))
    )
    (net (code "13") (name "/Code1_BufferOut") (class "Default")
      (node (ref "P3") (pin "4") (pinfunction "4_4") (pintype "passive"))
      (node (ref "U2") (pin "13") (pinfunction "3Y1_13") (pintype "output"))
    )
    (net (code "14") (name "/Code2") (class "Default")
      (node (ref "J13") (pin "16") (pinfunction "16_16") (pintype "passive"))
      (node (ref "U2") (pin "35") (pinfunction "3A2_35") (pintype "input"))
    )
    (net (code "15") (name "/Code2_BufferOut") (class "Default")
      (node (ref "P3") (pin "5") (pinfunction "5_5") (pintype "passive"))
      (node (ref "U2") (pin "14") (pinfunction "3Y2_14") (pintype "output"))
    )
    (net (code "16") (name "/Code3") (class "Default")
      (node (ref "J13") (pin "18") (pinfunction "18_18") (pintype "passive"))
      (node (ref "U2") (pin "33") (pinfunction "3A3_33") (pintype "input"))
    )
    (net (code "17") (name "/Code3_BufferOut") (class "Default")
      (node (ref "P14") (pin "1") (pinfunction "1_1") (pintype "passive"))
      (node (ref "U2") (pin "16") (pinfunction "3Y3_16") (pintype "output"))
    )
    (net (code "18") (name "/Code4") (class "Default")
      (node (ref "J13") (pin "17") (pinfunction "17_17") (pintype "passive"))
      (node (ref "U2") (pin "32") (pinfunction "3A4_32") (pintype "input"))
    )
    (net (code "19") (name "/Code4_BufferOut") (class "Default")
      (node (ref "P14") (pin "2") (pinfunction "2_2") (pintype "passive"))
      (node (ref "U2") (pin "17") (pinfunction "3Y4_17") (pintype "output"))
    )
    (net (code "20") (name "/Code5") (class "Default")
      (node (ref "J13") (pin "15") (pinfunction "15_15") (pintype "passive"))
      (node (ref "U2") (pin "30") (pinfunction "4A1_30") (pintype "input"))
    )
    (net (code "21") (name "/Code5_BufferOut") (class "Default")
      (node (ref "P14") (pin "3") (pinfunction "3_3") (pintype "passive"))
      (node (ref "U2") (pin "19") (pinfunction "4Y1_19") (pintype "output"))
    )
    (net (code "22") (name "/Code6") (class "Default")
      (node (ref "J13") (pin "13") (pinfunction "13_13") (pintype "passive"))
      (node (ref "U2") (pin "29") (pinfunction "4A2_29") (pintype "input"))
    )
    (net (code "23") (name "/Code6_BufferOut") (class "Default")
      (node (ref "P14") (pin "4") (pinfunction "4_4") (pintype "passive"))
      (node (ref "U2") (pin "20") (pinfunction "4Y2_20") (pintype "output"))
    )
    (net (code "24") (name "/Code7") (class "Default")
      (node (ref "J13") (pin "11") (pinfunction "11_11") (pintype "passive"))
      (node (ref "U2") (pin "27") (pinfunction "4A3_27") (pintype "input"))
    )
    (net (code "25") (name "/Code7_BufferOut") (class "Default")
      (node (ref "P14") (pin "5") (pinfunction "5_5") (pintype "passive"))
      (node (ref "U2") (pin "22") (pinfunction "4Y3_22") (pintype "output"))
    )
    (net (code "26") (name "/Code8") (class "Default")
      (node (ref "J13") (pin "9") (pinfunction "9_9") (pintype "passive"))
      (node (ref "U2") (pin "26") (pinfunction "4A4_26") (pintype "input"))
    )
    (net (code "27") (name "/Code8_BufferOut") (class "Default")
      (node (ref "P14") (pin "6") (pinfunction "6_6") (pintype "passive"))
      (node (ref "U2") (pin "23") (pinfunction "4Y4_23") (pintype "output"))
    )
    (net (code "28") (name "/EOC") (class "Default")
      (node (ref "J13") (pin "10") (pinfunction "10_10") (pintype "passive"))
      (node (ref "U2") (pin "38") (pinfunction "2A3_38") (pintype "input"))
    )
    (net (code "29") (name "/EOC_BufferOut") (class "Default")
      (node (ref "P3") (pin "2") (pinfunction "2_2") (pintype "passive"))
      (node (ref "U2") (pin "11") (pinfunction "2Y3_11") (pintype "output"))
    )
    (net (code "30") (name "/For_AVDD_ESD_1.5V") (class "Default")
      (node (ref "C12") (pin "2") (pinfunction "2_2") (pintype "passive"))
      (node (ref "R20") (pin "3") (pinfunction "CW_3") (pintype "passive"))
      (node (ref "U8") (pin "5") (pinfunction "OUT_5") (pintype "output"))
    )
    (net (code "31") (name "/For_AVDD_ESD_1V") (class "Default")
      (node (ref "J10") (pin "5") (pinfunction "5_5") (pintype "passive"))
      (node (ref "P9") (pin "2") (pinfunction "2_2") (pintype "passive"))
    )
    (net (code "32") (name "/For_DVDD_1.5V") (class "Default")
      (node (ref "C14") (pin "2") (pinfunction "2_2") (pintype "passive"))
      (node (ref "R19") (pin "3") (pinfunction "CW_3") (pintype "passive"))
      (node (ref "U7") (pin "5") (pinfunction "OUT_5") (pintype "output"))
    )
    (net (code "33") (name "/For_DVDD_1V") (class "Default")
      (node (ref "J13") (pin "3") (pinfunction "3_3") (pintype "passive"))
      (node (ref "P2") (pin "1") (pinfunction "1_1") (pintype "passive"))
      (node (ref "P2") (pin "2") (pinfunction "2_2") (pintype "passive"))
      (node (ref "P8") (pin "2") (pinfunction "2_2") (pintype "passive"))
    )
    (net (code "34") (name "/For_VCM_0.5V") (class "Default")
      (node (ref "J10") (pin "3") (pinfunction "3_3") (pintype "passive"))
      (node (ref "P10") (pin "2") (pinfunction "2_2") (pintype "passive"))
    )
    (net (code "35") (name "/For_VCM_1.5V") (class "Default")
      (node (ref "C16") (pin "2") (pinfunction "2_2") (pintype "passive"))
      (node (ref "R30") (pin "3") (pinfunction "CW_3") (pintype "passive"))
      (node (ref "U9") (pin "5") (pinfunction "OUT_5") (pintype "output"))
    )
    (net (code "36") (name "/IN_T12_N") (class "Default")
      (node (ref "J10") (pin "2") (pinfunction "2_2") (pintype "passive"))
      (node (ref "J9") (pin "2") (pinfunction "2_2") (pintype "passive"))
    )
    (net (code "37") (name "/IN_T12_P") (class "Default")
      (node (ref "J10") (pin "4") (pinfunction "4_4") (pintype "passive"))
      (node (ref "J12") (pin "2") (pinfunction "2_2") (pintype "passive"))
    )
    (net (code "38") (name "/LDO_OUT_2.5V") (class "Default")
      (node (ref "C29") (pin "1") (pinfunction "1_1") (pintype "passive"))
      (node (ref "P1") (pin "2") (pinfunction "2_2") (pintype "passive"))
      (node (ref "U11") (pin "5") (pinfunction "EN_5") (pintype "input"))
      (node (ref "U11") (pin "6") (pinfunction "IN_6") (pintype "power_in"))
    )
    (net (code "39") (name "/MUX0") (class "Default")
      (node (ref "J13") (pin "8") (pinfunction "8_8") (pintype "passive"))
      (node (ref "P7") (pin "1") (pinfunction "1_1") (pintype "passive"))
    )
    (net (code "40") (name "/MUX1") (class "Default")
      (node (ref "J13") (pin "7") (pinfunction "7_7") (pintype "passive"))
      (node (ref "P7") (pin "2") (pinfunction "2_2") (pintype "passive"))
    )
    (net (code "41") (name "/SEDE_0.5V") (class "Default")
      (node (ref "C25") (pin "1") (pinfunction "1_1") (pintype "passive"))
      (node (ref "TP4") (pin "1") (pinfunction "1_1") (pintype "passive"))
      (node (ref "U11") (pin "1") (pinfunction "OUT_1") (pintype "passive"))
      (node (ref "U11") (pin "2") (pinfunction "ADJ/SENSE_2") (pintype "passive"))
      (node (ref "U5") (pin "2") (pinfunction "VOCM_2") (pintype "power_in"))
    )
    (net (code "42") (name "/SEDE_INPUT") (class "Default")
      (node (ref "P12") (pin "1") (pinfunction "1_1") (pintype "passive"))
      (node (ref "R22") (pin "1") (pinfunction "1_1") (pintype "passive"))
      (node (ref "TP3") (pin "1") (pinfunction "1_1") (pintype "passive"))
    )
    (net (code "43") (name "/VDD_2.5V") (class "Default")
      (node (ref "C11") (pin "2") (pinfunction "2_2") (pintype "passive"))
      (node (ref "C13") (pin "2") (pinfunction "2_2") (pintype "passive"))
      (node (ref "C15") (pin "2") (pinfunction "2_2") (pintype "passive"))
      (node (ref "C2") (pin "1") (pinfunction "1_1") (pintype "passive"))
      (node (ref "C4") (pin "1") (pinfunction "1_1") (pintype "passive"))
      (node (ref "J13") (pin "1") (pinfunction "1_1") (pintype "passive"))
      (node (ref "J3") (pin "1") (pinfunction "1_1") (pintype "passive"))
      (node (ref "U7") (pin "1") (pinfunction "IN_1") (pintype "input"))
      (node (ref "U7") (pin "3") (pinfunction "EN_3") (pintype "input"))
      (node (ref "U8") (pin "1") (pinfunction "IN_1") (pintype "input"))
      (node (ref "U8") (pin "3") (pinfunction "EN_3") (pintype "input"))
      (node (ref "U9") (pin "1") (pinfunction "IN_1") (pintype "input"))
      (node (ref "U9") (pin "3") (pinfunction "EN_3") (pintype "input"))
    )
    (net (code "44") (name "/V_SIN_IN_N") (class "Default")
      (node (ref "J11") (pin "1") (pinfunction "1_1") (pintype "passive"))
      (node (ref "J9") (pin "1") (pinfunction "1_1") (pintype "passive"))
      (node (ref "R28") (pin "2") (pinfunction "2_2") (pintype "passive"))
    )
    (net (code "45") (name "/V_SIN_IN_P") (class "Default")
      (node (ref "C17") (pin "1") (pinfunction "1_1") (pintype "passive"))
      (node (ref "J12") (pin "3") (pinfunction "3_3") (pintype "passive"))
      (node (ref "J2") (pin "1") (pinfunction "1_1") (pintype "passive"))
      (node (ref "R17") (pin "1") (pinfunction "1_1") (pintype "passive"))
      (node (ref "TP1") (pin "1") (pinfunction "1_1") (pintype "passive"))
    )
    (net (code "46") (name "2.5V_Buffer") (class "Default")
      (node (ref "C28") (pin "2") (pinfunction "2_2") (pintype "passive"))
      (node (ref "C9") (pin "2") (pinfunction "2_2") (pintype "passive"))
      (node (ref "U1") (pin "5") (pinfunction "VOUT_5") (pintype "power_in"))
      (node (ref "U2") (pin "1") (pinfunction "1~{OE}_1") (pintype "input"))
      (node (ref "U2") (pin "18") (pinfunction "VCC_18") (pintype "power_in"))
      (node (ref "U2") (pin "31") (pinfunction "VCC_31") (pintype "open_emitter"))
      (node (ref "U2") (pin "42") (pinfunction "VCC_42") (pintype "power_in"))
      (node (ref "U2") (pin "7") (pinfunction "VCC_7") (pintype "power_in"))
    )
    (net (code "47") (name "AGND") (class "Default")
      (node (ref "C11") (pin "1") (pinfunction "1_1") (pintype "passive"))
      (node (ref "C12") (pin "1") (pinfunction "1_1") (pintype "passive"))
      (node (ref "C13") (pin "1") (pinfunction "1_1") (pintype "passive"))
      (node (ref "C14") (pin "1") (pinfunction "1_1") (pintype "passive"))
      (node (ref "C15") (pin "1") (pinfunction "1_1") (pintype "passive"))
      (node (ref "C16") (pin "1") (pinfunction "1_1") (pintype "passive"))
      (node (ref "C2") (pin "2") (pinfunction "2_2") (pintype "passive"))
      (node (ref "C4") (pin "2") (pinfunction "2_2") (pintype "passive"))
      (node (ref "J10") (pin "1") (pinfunction "1_1") (pintype "passive"))
      (node (ref "J13") (pin "2") (pinfunction "2_2") (pintype "passive"))
      (node (ref "J13") (pin "4") (pinfunction "4_4") (pintype "passive"))
      (node (ref "J4") (pin "1") (pinfunction "1_1") (pintype "passive"))
      (node (ref "P5") (pin "1") (pinfunction "1_1") (pintype "passive"))
      (node (ref "P5") (pin "2") (pinfunction "2_2") (pintype "passive"))
      (node (ref "R18") (pin "1") (pinfunction "1_1") (pintype "passive"))
      (node (ref "R19") (pin "1") (pinfunction "CCW_1") (pintype "passive"))
      (node (ref "R20") (pin "1") (pinfunction "CCW_1") (pintype "passive"))
      (node (ref "R21") (pin "2") (pinfunction "2_2") (pintype "passive"))
      (node (ref "R23") (pin "2") (pinfunction "2_2") (pintype "passive"))
      (node (ref "R30") (pin "1") (pinfunction "CCW_1") (pintype "passive"))
      (node (ref "R31") (pin "2") (pinfunction "2_2") (pintype "passive"))
      (node (ref "TP5") (pin "1") (pinfunction "1_1") (pintype "passive"))
      (node (ref "U7") (pin "2") (pinfunction "GND_2") (pintype "power_in"))
      (node (ref "U8") (pin "2") (pinfunction "GND_2") (pintype "power_in"))
      (node (ref "U9") (pin "2") (pinfunction "GND_2") (pintype "power_in"))
    )
    (net (code "48") (name "DGND") (class "Default")
      (node (ref "C1") (pin "2") (pinfunction "2_2") (pintype "passive"))
      (node (ref "C10") (pin "2") (pinfunction "2_2") (pintype "passive"))
      (node (ref "C18") (pin "2") (pinfunction "2_2") (pintype "passive"))
      (node (ref "C19") (pin "2") (pinfunction "2_2") (pintype "passive"))
      (node (ref "C20") (pin "2") (pinfunction "2_2") (pintype "passive"))
      (node (ref "C21") (pin "2") (pinfunction "2_2") (pintype "passive"))
      (node (ref "C22") (pin "1") (pinfunction "1_1") (pintype "passive"))
      (node (ref "C23") (pin "2") (pinfunction "2_2") (pintype "passive"))
      (node (ref "C24") (pin "1") (pinfunction "1_1") (pintype "passive"))
      (node (ref "C25") (pin "2") (pinfunction "2_2") (pintype "passive"))
      (node (ref "C27") (pin "1") (pinfunction "1_1") (pintype "passive"))
      (node (ref "C28") (pin "1") (pinfunction "1_1") (pintype "passive"))
      (node (ref "C29") (pin "2") (pinfunction "2_2") (pintype "passive"))
      (node (ref "C3") (pin "2") (pinfunction "2_2") (pintype "passive"))
      (node (ref "C5") (pin "2") (pinfunction "2_2") (pintype "passive"))
      (node (ref "C6") (pin "2") (pinfunction "2_2") (pintype "passive"))
      (node (ref "C7") (pin "1") (pinfunction "1_1") (pintype "passive"))
      (node (ref "C8") (pin "1") (pinfunction "1_1") (pintype "passive"))
      (node (ref "C9") (pin "1") (pinfunction "1_1") (pintype "passive"))
      (node (ref "J5") (pin "1") (pinfunction "1_1") (pintype "passive"))
      (node (ref "J8") (pin "1") (pinfunction "1_1") (pintype "passive"))
      (node (ref "P11") (pin "1") (pinfunction "1_1") (pintype "passive"))
      (node (ref "P11") (pin "2") (pinfunction "2_2") (pintype "passive"))
      (node (ref "P13") (pin "1") (pinfunction "1_1") (pintype "passive"))
      (node (ref "P13") (pin "2") (pinfunction "2_2") (pintype "passive"))
      (node (ref "P3") (pin "6") (pinfunction "6_6") (pintype "passive"))
      (node (ref "P6") (pin "1") (pinfunction "1_1") (pintype "passive"))
      (node (ref "P6") (pin "2") (pinfunction "2_2") (pintype "passive"))
      (node (ref "R1") (pin "2") (pinfunction "2_2") (pintype "passive"))
      (node (ref "R17") (pin "2") (pinfunction "2_2") (pintype "passive"))
      (node (ref "R18") (pin "2") (pinfunction "2_2") (pintype "passive"))
      (node (ref "R27") (pin "1") (pinfunction "1_1") (pintype "passive"))
      (node (ref "R28") (pin "1") (pinfunction "1_1") (pintype "passive"))
      (node (ref "U1") (pin "2") (pinfunction "GND_2") (pintype "power_in"))
      (node (ref "U10") (pin "1") (pinfunction "GND_1") (pintype "power_in"))
      (node (ref "U10") (pin "3") (pinfunction "GND_3") (pintype "power_in"))
      (node (ref "U11") (pin "3") (pinfunction "GND_3") (pintype "power_in"))
      (node (ref "U11") (pin "7") (pinfunction "GND_7") (pintype "power_in"))
      (node (ref "U2") (pin "10") (pinfunction "GND_10") (pintype "power_in"))
      (node (ref "U2") (pin "15") (pinfunction "GND_15") (pintype "power_in"))
      (node (ref "U2") (pin "21") (pinfunction "GND_21") (pintype "power_in"))
      (node (ref "U2") (pin "24") (pinfunction "4~{OE}_24") (pintype "input"))
      (node (ref "U2") (pin "25") (pinfunction "3~{OE}_25") (pintype "input"))
      (node (ref "U2") (pin "28") (pinfunction "GND_28") (pintype "power_in"))
      (node (ref "U2") (pin "34") (pinfunction "GND_34") (pintype "power_in"))
      (node (ref "U2") (pin "39") (pinfunction "GND_39") (pintype "power_in"))
      (node (ref "U2") (pin "4") (pinfunction "GND_4") (pintype "power_in"))
      (node (ref "U2") (pin "41") (pinfunction "2A1_41") (pintype "input"))
      (node (ref "U2") (pin "43") (pinfunction "1A4_43") (pintype "input"))
      (node (ref "U2") (pin "44") (pinfunction "1A3_44") (pintype "input"))
      (node (ref "U2") (pin "45") (pinfunction "GND_45") (pintype "power_in"))
      (node (ref "U2") (pin "46") (pinfunction "1A2_46") (pintype "input"))
      (node (ref "U2") (pin "47") (pinfunction "1A1_47") (pintype "input"))
      (node (ref "U2") (pin "48") (pinfunction "2~{OE}_48") (pintype "input"))
      (node (ref "U3") (pin "2") (pinfunction "GND_2") (pintype "power_in"))
    )
    (net (code "49") (name "Net-(P4-Pad1)") (class "Default")
      (node (ref "P4") (pin "1") (pinfunction "1_1") (pintype "passive"))
      (node (ref "R6") (pin "2") (pinfunction "2_2") (pintype "passive"))
      (node (ref "TP2") (pin "1") (pinfunction "1_1") (pintype "passive"))
    )
    (net (code "50") (name "Net-(R19-WIPER)") (class "Default")
      (node (ref "P8") (pin "1") (pinfunction "1_1") (pintype "passive"))
      (node (ref "R19") (pin "2") (pinfunction "WIPER_2") (pintype "passive"))
      (node (ref "R21") (pin "1") (pinfunction "1_1") (pintype "passive"))
    )
    (net (code "51") (name "Net-(R20-WIPER)") (class "Default")
      (node (ref "P9") (pin "1") (pinfunction "1_1") (pintype "passive"))
      (node (ref "R20") (pin "2") (pinfunction "WIPER_2") (pintype "passive"))
      (node (ref "R23") (pin "1") (pinfunction "1_1") (pintype "passive"))
    )
    (net (code "52") (name "Net-(R30-WIPER)") (class "Default")
      (node (ref "P10") (pin "1") (pinfunction "1_1") (pintype "passive"))
      (node (ref "R30") (pin "2") (pinfunction "WIPER_2") (pintype "passive"))
      (node (ref "R31") (pin "1") (pinfunction "1_1") (pintype "passive"))
      (node (ref "TP6") (pin "1") (pinfunction "1_1") (pintype "passive"))
    )
    (net (code "53") (name "Net-(U3-VOUT)") (class "Default")
      (node (ref "C7") (pin "2") (pinfunction "2_2") (pintype "passive"))
      (node (ref "P1") (pin "1") (pinfunction "1_1") (pintype "passive"))
      (node (ref "U3") (pin "5") (pinfunction "VOUT_5") (pintype "power_in"))
    )
    (net (code "54") (name "Net-(U4--IN)") (class "Default")
      (node (ref "P12") (pin "2") (pinfunction "2_2") (pintype "passive"))
      (node (ref "U4") (pin "2") (pinfunction "-IN_2") (pintype "input"))
      (node (ref "U4") (pin "6") (pinfunction "VOUT_6") (pintype "output"))
    )
    (net (code "55") (name "Net-(U10-0.5fC{slash}*fC)") (class "Default")
      (node (ref "J14") (pin "2") (pinfunction "2_2") (pintype "passive"))
      (node (ref "U10") (pin "5") (pinfunction "0.5fC/*fC_5") (pintype "passive"))
    )
    (net (code "56") (name "Net-(U10-VIN)") (class "Default")
      (node (ref "C17") (pin "2") (pinfunction "2_2") (pintype "passive"))
      (node (ref "U10") (pin "2") (pinfunction "VIN_2") (pintype "input"))
    )
    (net (code "57") (name "Net-(U10-VOUT)") (class "Default")
      (node (ref "R6") (pin "1") (pinfunction "1_1") (pintype "passive"))
      (node (ref "U10") (pin "8") (pinfunction "VOUT_8") (pintype "output"))
    )
    (net (code "58") (name "unconnected-(J1-MNT_1-Pad2)") (class "Default")
      (node (ref "J1") (pin "2") (pinfunction "MNT_1_2") (pintype "passive+no_connect"))
    )
    (net (code "59") (name "unconnected-(J1-MNT_2-Pad3)") (class "Default")
      (node (ref "J1") (pin "3") (pinfunction "MNT_2_3") (pintype "passive+no_connect"))
    )
    (net (code "60") (name "unconnected-(J1-MNT_3-Pad4)") (class "Default")
      (node (ref "J1") (pin "4") (pinfunction "MNT_3_4") (pintype "passive+no_connect"))
    )
    (net (code "61") (name "unconnected-(J1-MNT_4-Pad5)") (class "Default")
      (node (ref "J1") (pin "5") (pinfunction "MNT_4_5") (pintype "passive+no_connect"))
    )
    (net (code "62") (name "unconnected-(J2-MNT_1-Pad2)") (class "Default")
      (node (ref "J2") (pin "2") (pinfunction "MNT_1_2") (pintype "passive+no_connect"))
    )
    (net (code "63") (name "unconnected-(J2-MNT_2-Pad3)") (class "Default")
      (node (ref "J2") (pin "3") (pinfunction "MNT_2_3") (pintype "passive+no_connect"))
    )
    (net (code "64") (name "unconnected-(J2-MNT_3-Pad4)") (class "Default")
      (node (ref "J2") (pin "4") (pinfunction "MNT_3_4") (pintype "passive+no_connect"))
    )
    (net (code "65") (name "unconnected-(J2-MNT_4-Pad5)") (class "Default")
      (node (ref "J2") (pin "5") (pinfunction "MNT_4_5") (pintype "passive+no_connect"))
    )
    (net (code "66") (name "unconnected-(J3-MNT_1-Pad2)") (class "Default")
      (node (ref "J3") (pin "2") (pinfunction "MNT_1_2") (pintype "passive+no_connect"))
    )
    (net (code "67") (name "unconnected-(J3-MNT_2-Pad3)") (class "Default")
      (node (ref "J3") (pin "3") (pinfunction "MNT_2_3") (pintype "passive+no_connect"))
    )
    (net (code "68") (name "unconnected-(J3-MNT_3-Pad4)") (class "Default")
      (node (ref "J3") (pin "4") (pinfunction "MNT_3_4") (pintype "passive+no_connect"))
    )
    (net (code "69") (name "unconnected-(J3-MNT_4-Pad5)") (class "Default")
      (node (ref "J3") (pin "5") (pinfunction "MNT_4_5") (pintype "passive+no_connect"))
    )
    (net (code "70") (name "unconnected-(J4-MNT_1-Pad2)") (class "Default")
      (node (ref "J4") (pin "2") (pinfunction "MNT_1_2") (pintype "passive+no_connect"))
    )
    (net (code "71") (name "unconnected-(J4-MNT_2-Pad3)") (class "Default")
      (node (ref "J4") (pin "3") (pinfunction "MNT_2_3") (pintype "passive+no_connect"))
    )
    (net (code "72") (name "unconnected-(J4-MNT_3-Pad4)") (class "Default")
      (node (ref "J4") (pin "4") (pinfunction "MNT_3_4") (pintype "passive+no_connect"))
    )
    (net (code "73") (name "unconnected-(J4-MNT_4-Pad5)") (class "Default")
      (node (ref "J4") (pin "5") (pinfunction "MNT_4_5") (pintype "passive+no_connect"))
    )
    (net (code "74") (name "unconnected-(J5-MNT_1-Pad2)") (class "Default")
      (node (ref "J5") (pin "2") (pinfunction "MNT_1_2") (pintype "passive+no_connect"))
    )
    (net (code "75") (name "unconnected-(J5-MNT_2-Pad3)") (class "Default")
      (node (ref "J5") (pin "3") (pinfunction "MNT_2_3") (pintype "passive+no_connect"))
    )
    (net (code "76") (name "unconnected-(J5-MNT_3-Pad4)") (class "Default")
      (node (ref "J5") (pin "4") (pinfunction "MNT_3_4") (pintype "passive+no_connect"))
    )
    (net (code "77") (name "unconnected-(J5-MNT_4-Pad5)") (class "Default")
      (node (ref "J5") (pin "5") (pinfunction "MNT_4_5") (pintype "passive+no_connect"))
    )
    (net (code "78") (name "unconnected-(J6-MNT_1-Pad2)") (class "Default")
      (node (ref "J6") (pin "2") (pinfunction "MNT_1_2") (pintype "passive+no_connect"))
    )
    (net (code "79") (name "unconnected-(J6-MNT_2-Pad3)") (class "Default")
      (node (ref "J6") (pin "3") (pinfunction "MNT_2_3") (pintype "passive+no_connect"))
    )
    (net (code "80") (name "unconnected-(J6-MNT_3-Pad4)") (class "Default")
      (node (ref "J6") (pin "4") (pinfunction "MNT_3_4") (pintype "passive+no_connect"))
    )
    (net (code "81") (name "unconnected-(J6-MNT_4-Pad5)") (class "Default")
      (node (ref "J6") (pin "5") (pinfunction "MNT_4_5") (pintype "passive+no_connect"))
    )
    (net (code "82") (name "unconnected-(J7-MNT_1-Pad2)") (class "Default")
      (node (ref "J7") (pin "2") (pinfunction "MNT_1_2") (pintype "passive+no_connect"))
    )
    (net (code "83") (name "unconnected-(J7-MNT_2-Pad3)") (class "Default")
      (node (ref "J7") (pin "3") (pinfunction "MNT_2_3") (pintype "passive+no_connect"))
    )
    (net (code "84") (name "unconnected-(J7-MNT_3-Pad4)") (class "Default")
      (node (ref "J7") (pin "4") (pinfunction "MNT_3_4") (pintype "passive+no_connect"))
    )
    (net (code "85") (name "unconnected-(J7-MNT_4-Pad5)") (class "Default")
      (node (ref "J7") (pin "5") (pinfunction "MNT_4_5") (pintype "passive+no_connect"))
    )
    (net (code "86") (name "unconnected-(J8-MNT_1-Pad2)") (class "Default")
      (node (ref "J8") (pin "2") (pinfunction "MNT_1_2") (pintype "passive+no_connect"))
    )
    (net (code "87") (name "unconnected-(J8-MNT_2-Pad3)") (class "Default")
      (node (ref "J8") (pin "3") (pinfunction "MNT_2_3") (pintype "passive+no_connect"))
    )
    (net (code "88") (name "unconnected-(J8-MNT_3-Pad4)") (class "Default")
      (node (ref "J8") (pin "4") (pinfunction "MNT_3_4") (pintype "passive+no_connect"))
    )
    (net (code "89") (name "unconnected-(J8-MNT_4-Pad5)") (class "Default")
      (node (ref "J8") (pin "5") (pinfunction "MNT_4_5") (pintype "passive+no_connect"))
    )
    (net (code "90") (name "unconnected-(J11-MNT_1-Pad2)") (class "Default")
      (node (ref "J11") (pin "2") (pinfunction "MNT_1_2") (pintype "passive+no_connect"))
    )
    (net (code "91") (name "unconnected-(J11-MNT_2-Pad3)") (class "Default")
      (node (ref "J11") (pin "3") (pinfunction "MNT_2_3") (pintype "passive+no_connect"))
    )
    (net (code "92") (name "unconnected-(J11-MNT_3-Pad4)") (class "Default")
      (node (ref "J11") (pin "4") (pinfunction "MNT_3_4") (pintype "passive+no_connect"))
    )
    (net (code "93") (name "unconnected-(J11-MNT_4-Pad5)") (class "Default")
      (node (ref "J11") (pin "5") (pinfunction "MNT_4_5") (pintype "passive+no_connect"))
    )
    (net (code "94") (name "unconnected-(U1-NC-Pad4)") (class "Default")
      (node (ref "U1") (pin "4") (pinfunction "NC_4") (pintype "passive+no_connect"))
    )
    (net (code "95") (name "unconnected-(U2-1Y1-Pad2)") (class "Default")
      (node (ref "U2") (pin "2") (pinfunction "1Y1_2") (pintype "output+no_connect"))
    )
    (net (code "96") (name "unconnected-(U2-1Y2-Pad3)") (class "Default")
      (node (ref "U2") (pin "3") (pinfunction "1Y2_3") (pintype "output+no_connect"))
    )
    (net (code "97") (name "unconnected-(U2-1Y3-Pad5)") (class "Default")
      (node (ref "U2") (pin "5") (pinfunction "1Y3_5") (pintype "output+no_connect"))
    )
    (net (code "98") (name "unconnected-(U2-1Y4-Pad6)") (class "Default")
      (node (ref "U2") (pin "6") (pinfunction "1Y4_6") (pintype "output+no_connect"))
    )
    (net (code "99") (name "unconnected-(U2-2Y1-Pad8)") (class "Default")
      (node (ref "U2") (pin "8") (pinfunction "2Y1_8") (pintype "output+no_connect"))
    )
    (net (code "100") (name "unconnected-(U3-NC-Pad4)") (class "Default")
      (node (ref "U3") (pin "4") (pinfunction "NC_4") (pintype "passive+no_connect"))
    )
    (net (code "101") (name "unconnected-(U4-NC-Pad5)") (class "Default")
      (node (ref "U4") (pin "5") (pinfunction "NC_5") (pintype "passive+no_connect"))
    )
    (net (code "102") (name "unconnected-(U4-NULL-Pad1)") (class "Default")
      (node (ref "U4") (pin "1") (pinfunction "NULL_1") (pintype "input+no_connect"))
    )
    (net (code "103") (name "unconnected-(U4-NULL-Pad8)") (class "Default")
      (node (ref "U4") (pin "8") (pinfunction "NULL_8") (pintype "input+no_connect"))
    )
    (net (code "104") (name "unconnected-(U5-~{DISABLE}-Pad7)") (class "Default")
      (node (ref "U5") (pin "7") (pinfunction "~{DISABLE}_7") (pintype "passive+no_connect"))
    )
    (net (code "105") (name "unconnected-(U7-NC{slash}FB-Pad4)") (class "Default")
      (node (ref "U7") (pin "4") (pinfunction "NC/FB_4") (pintype "passive+no_connect"))
    )
    (net (code "106") (name "unconnected-(U8-NC{slash}FB-Pad4)") (class "Default")
      (node (ref "U8") (pin "4") (pinfunction "NC/FB_4") (pintype "passive+no_connect"))
    )
    (net (code "107") (name "unconnected-(U9-NC{slash}FB-Pad4)") (class "Default")
      (node (ref "U9") (pin "4") (pinfunction "NC/FB_4") (pintype "passive+no_connect"))
    )
    (net (code "108") (name "unconnected-(U11-PG-Pad4)") (class "Default")
      (node (ref "U11") (pin "4") (pinfunction "PG_4") (pintype "output+no_connect"))
    )
  )
)
